# relay-unit-atmega.net
KiCad netlist of a schematic drawn in EAGLE
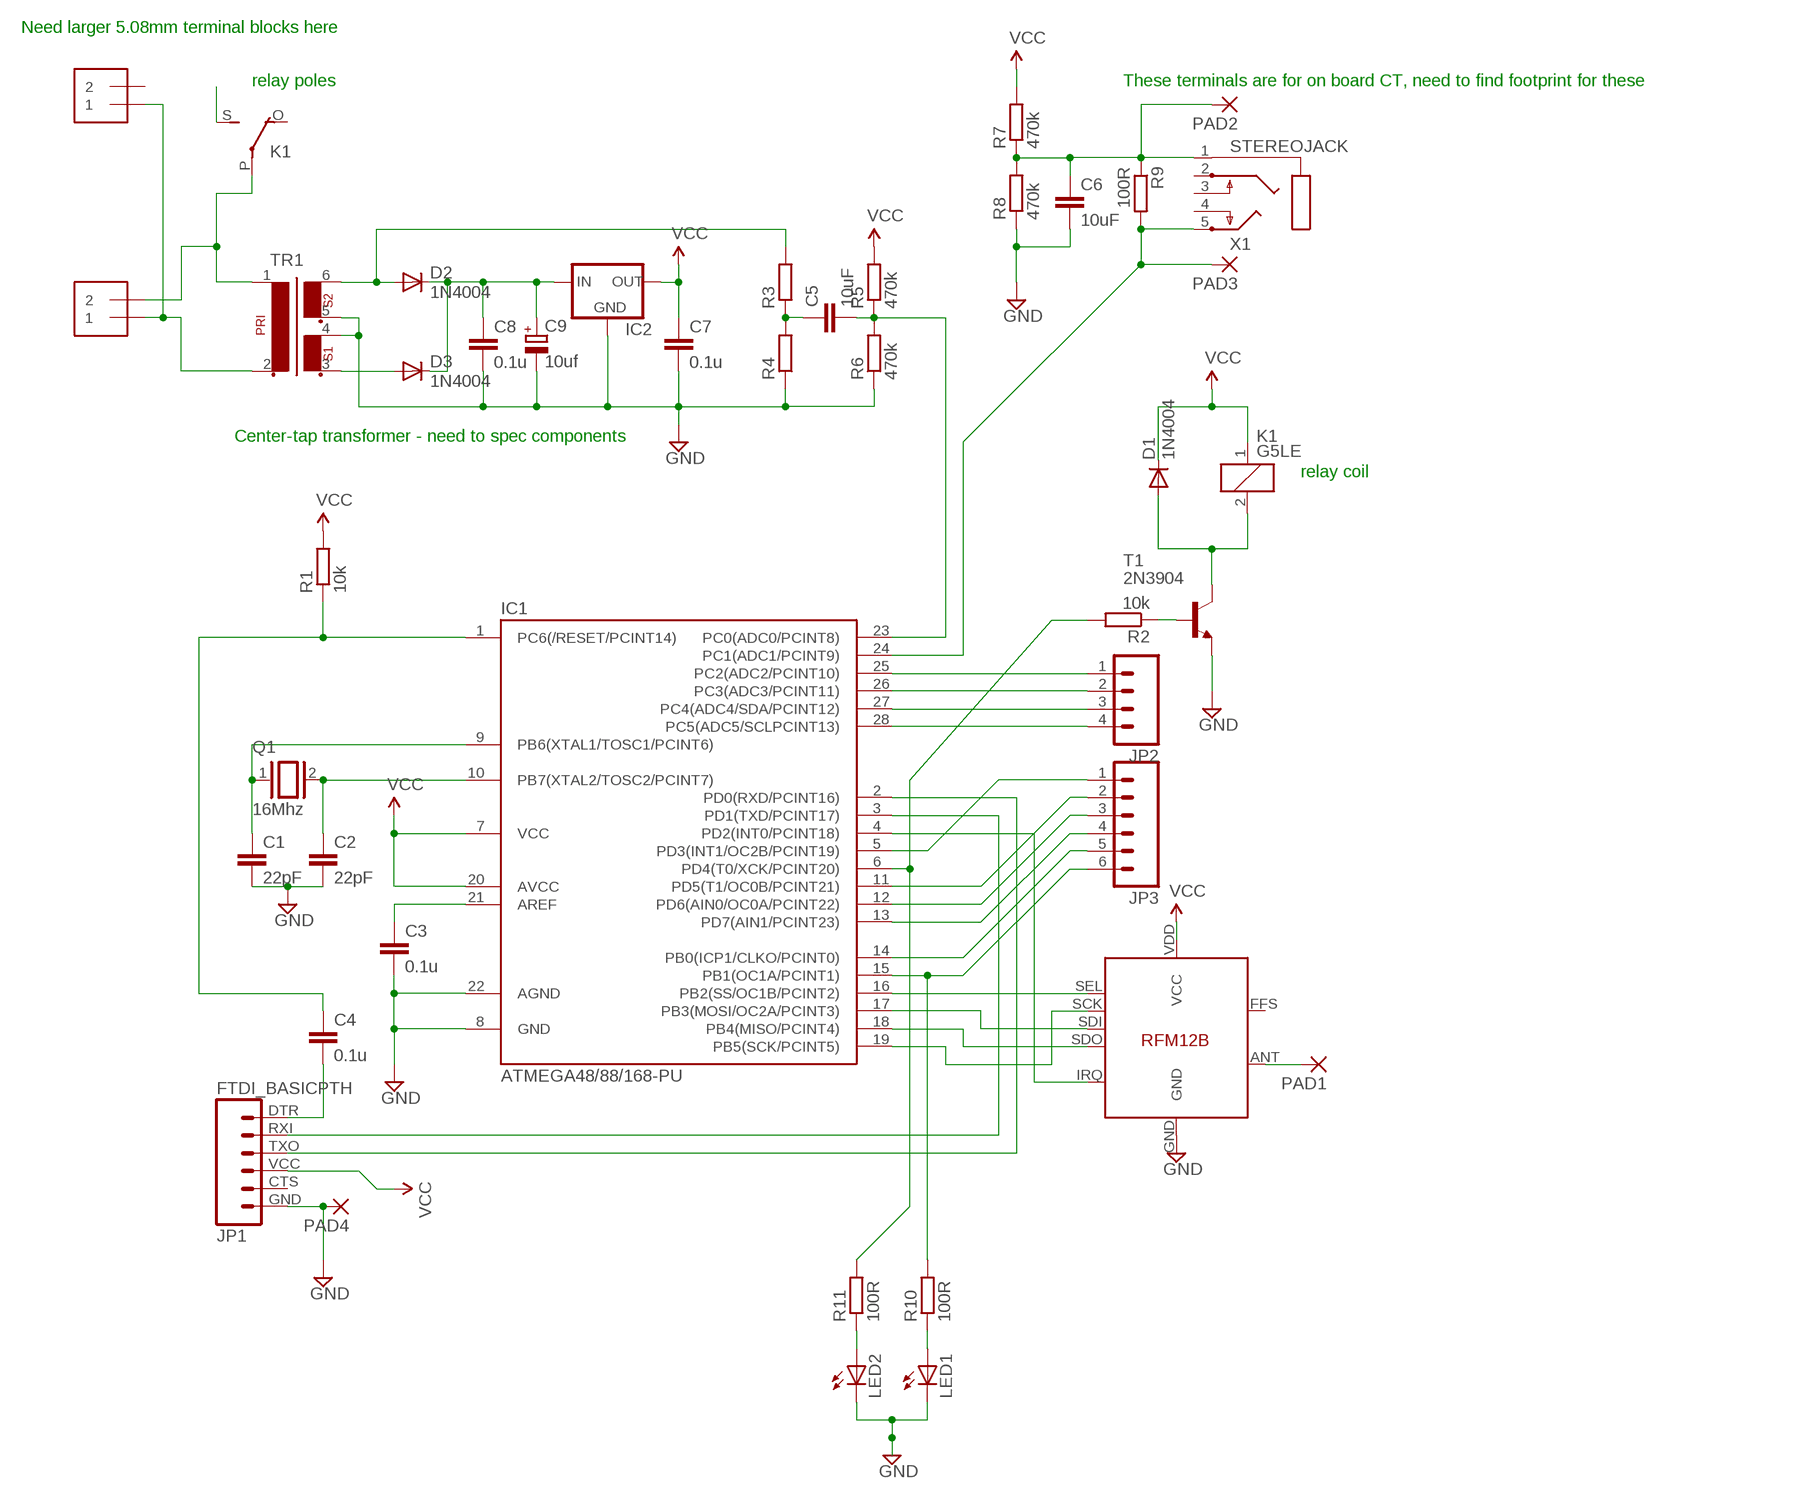
[diagram p0: schematic, sheet 1]

(export (version "E")
  (design (tool "Eeschema 10.0.6"))
  (components
    (comp (ref "C1")
      (value "22pF")
      (footprint "eagle-import:C2.5-2")
      (libsource (lib "eagle-import") (part "C2.5/2"))
    )
    (comp (ref "C2")
      (value "22pF")
      (footprint "eagle-import:C2.5-2")
      (libsource (lib "eagle-import") (part "C2.5/2"))
    )
    (comp (ref "C3")
      (value "0.1u")
      (footprint "eagle-import:C025-024X044")
      (libsource (lib "eagle-import") (part "C-EU025-024X044"))
    )
    (comp (ref "C4")
      (value "0.1u")
      (footprint "eagle-import:C025-024X044")
      (libsource (lib "eagle-import") (part "C-EU025-024X044"))
    )
    (comp (ref "C5")
      (value "10uF")
      (footprint "eagle-import:C025-024X044")
      (libsource (lib "eagle-import") (part "C-EU025-024X044"))
    )
    (comp (ref "C6")
      (value "10uF")
      (footprint "eagle-import:C025-024X044")
      (libsource (lib "eagle-import") (part "C-EU025-024X044"))
    )
    (comp (ref "C7")
      (value "0.1u")
      (footprint "eagle-import:C025-024X044")
      (libsource (lib "eagle-import") (part "C-EU025-024X044"))
    )
    (comp (ref "C8")
      (value "0.1u")
      (footprint "eagle-import:C025-024X044")
      (libsource (lib "eagle-import") (part "C-EU025-024X044"))
    )
    (comp (ref "C9")
      (value "10uf")
      (footprint "eagle-import:E1,8-4")
      (libsource (lib "eagle-import") (part "CPOL-EUE1.8-4"))
    )
    (comp (ref "D1")
      (value "1N4004")
      (footprint "eagle-import:DO41-10")
      (libsource (lib "eagle-import") (part "1N4004"))
    )
    (comp (ref "D2")
      (value "1N4004")
      (footprint "eagle-import:DO41-10")
      (libsource (lib "eagle-import") (part "1N4004"))
    )
    (comp (ref "D3")
      (value "1N4004")
      (footprint "eagle-import:DO41-10")
      (libsource (lib "eagle-import") (part "1N4004"))
    )
    (comp (ref "IC1")
      (value "ATMEGA48/88/168-PU")
      (footprint "eagle-import:DIL28-3")
      (libsource (lib "eagle-import") (part "ATMEGA48/88/168-PU"))
    )
    (comp (ref "IC2")
      (value "MCP1700TRI")
      (footprint "eagle-import:TO92")
      (libsource (lib "eagle-import") (part "MCP1700TRI"))
    )
    (comp (ref "J1")
      (value "1X2-3.5MM")
      (footprint "eagle-import:1X2-3.5MM")
      (libsource (lib "eagle-import") (part "1X2-3.5MM"))
    )
    (comp (ref "J2")
      (value "1X2-3.5MM")
      (footprint "eagle-import:1X2-3.5MM")
      (libsource (lib "eagle-import") (part "1X2-3.5MM"))
    )
    (comp (ref "JP1")
      (value "FTDI_BASICPTH")
      (footprint "eagle-import:FTDI_BASIC")
      (libsource (lib "eagle-import") (part "FTDI_BASICPTH"))
    )
    (comp (ref "JP2")
      (value "M04PTH")
      (footprint "eagle-import:1X04")
      (libsource (lib "eagle-import") (part "M04PTH"))
    )
    (comp (ref "JP3")
      (value "M06SIP")
      (footprint "eagle-import:1X06")
      (libsource (lib "eagle-import") (part "M06SIP"))
    )
    (comp (ref "K1")
      (value "G5LE")
      (footprint "eagle-import:G5LE")
      (libsource (lib "eagle-import") (part "G5LE"))
    )
    (comp (ref "LED1")
      (value "LED3MM")
      (footprint "eagle-import:LED3MM")
      (libsource (lib "eagle-import") (part "LED3MM"))
    )
    (comp (ref "LED2")
      (value "LED3MM")
      (footprint "eagle-import:LED3MM")
      (libsource (lib "eagle-import") (part "LED3MM"))
    )
    (comp (ref "PAD1")
      (value "1,6/0,8")
      (footprint "eagle-import:1,6_0,8")
      (libsource (lib "eagle-import") (part "1,6/0,8"))
    )
    (comp (ref "PAD2")
      (value "1,6/0,8")
      (footprint "eagle-import:1,6_0,8")
      (libsource (lib "eagle-import") (part "1,6/0,8"))
    )
    (comp (ref "PAD3")
      (value "1,6/0,8")
      (footprint "eagle-import:1,6_0,8")
      (libsource (lib "eagle-import") (part "1,6/0,8"))
    )
    (comp (ref "PAD4")
      (value "1,6/0,8")
      (footprint "eagle-import:1,6_0,8")
      (libsource (lib "eagle-import") (part "1,6/0,8"))
    )
    (comp (ref "Q1")
      (value "16Mhz")
      (footprint "eagle-import:QS")
      (libsource (lib "eagle-import") (part "XTAL/S"))
    )
    (comp (ref "R1")
      (value "10k")
      (footprint "eagle-import:0204_7")
      (libsource (lib "eagle-import") (part "R-EU_0204/7"))
    )
    (comp (ref "R2")
      (value "10k")
      (footprint "eagle-import:0204_7")
      (libsource (lib "eagle-import") (part "R-EU_0204/7"))
    )
    (comp (ref "R3")
      (value "R-EU_0204/7")
      (footprint "eagle-import:0204_7")
      (libsource (lib "eagle-import") (part "R-EU_0204/7"))
    )
    (comp (ref "R4")
      (value "R-EU_0204/7")
      (footprint "eagle-import:0204_7")
      (libsource (lib "eagle-import") (part "R-EU_0204/7"))
    )
    (comp (ref "R5")
      (value "470k")
      (footprint "eagle-import:0204_7")
      (libsource (lib "eagle-import") (part "R-EU_0204/7"))
    )
    (comp (ref "R6")
      (value "470k")
      (footprint "eagle-import:0204_7")
      (libsource (lib "eagle-import") (part "R-EU_0204/7"))
    )
    (comp (ref "R7")
      (value "470k")
      (footprint "eagle-import:0204_7")
      (libsource (lib "eagle-import") (part "R-EU_0204/7"))
    )
    (comp (ref "R8")
      (value "470k")
      (footprint "eagle-import:0204_7")
      (libsource (lib "eagle-import") (part "R-EU_0204/7"))
    )
    (comp (ref "R9")
      (value "100R")
      (footprint "eagle-import:0204_7")
      (libsource (lib "eagle-import") (part "R-EU_0204/7"))
    )
    (comp (ref "R10")
      (value "100R")
      (footprint "eagle-import:0204_7")
      (libsource (lib "eagle-import") (part "R-EU_0204/7"))
    )
    (comp (ref "R11")
      (value "100R")
      (footprint "eagle-import:0204_7")
      (libsource (lib "eagle-import") (part "R-EU_0204/7"))
    )
    (comp (ref "T1")
      (value "2N3904")
      (footprint "eagle-import:TO92")
      (libsource (lib "eagle-import") (part "2N3904"))
    )
    (comp (ref "TR1")
      (value "VP32")
      (footprint "eagle-import:VP32")
      (libsource (lib "eagle-import") (part "VP32"))
    )
    (comp (ref "U$1")
      (value "RFM12B")
      (footprint "eagle-import:RFM12B")
      (libsource (lib "eagle-import") (part "RFM12B"))
    )
    (comp (ref "X1")
      (value "STEREOJACK")
      (footprint "eagle-import:STX3100")
      (libsource (lib "eagle-import") (part "STEREOJACK"))
    )
  )
  (nets
    (net (code "1") (name "GND") (class "Default")
      (node (ref "C1") (pin "2") (pinfunction "2_2") (pintype "passive"))
      (node (ref "C2") (pin "2") (pinfunction "2_2") (pintype "passive"))
      (node (ref "C3") (pin "2") (pinfunction "2_2") (pintype "passive"))
      (node (ref "C6") (pin "2") (pinfunction "2_2") (pintype "passive"))
      (node (ref "C7") (pin "2") (pinfunction "2_2") (pintype "passive"))
      (node (ref "C8") (pin "2") (pinfunction "2_2") (pintype "passive"))
      (node (ref "C9") (pin "-") (pinfunction "-_-") (pintype "passive"))
      (node (ref "IC1") (pin "22") (pinfunction "AGND_22") (pintype "power_in"))
      (node (ref "IC1") (pin "8") (pinfunction "GND_8") (pintype "power_in"))
      (node (ref "IC2") (pin "1") (pinfunction "GND_1") (pintype "input"))
      (node (ref "JP1") (pin "GND") (pinfunction "6_GND") (pintype "passive"))
      (node (ref "LED1") (pin "K") (pinfunction "C_K") (pintype "passive"))
      (node (ref "LED2") (pin "K") (pinfunction "C_K") (pintype "passive"))
      (node (ref "PAD4") (pin "1") (pinfunction "P_1") (pintype "passive"))
      (node (ref "R4") (pin "1") (pinfunction "1_1") (pintype "passive"))
      (node (ref "R6") (pin "1") (pinfunction "1_1") (pintype "passive"))
      (node (ref "R8") (pin "1") (pinfunction "1_1") (pintype "passive"))
      (node (ref "T1") (pin "3") (pinfunction "E_3") (pintype "passive"))
      (node (ref "TR1") (pin "4") (pinfunction "4_4") (pintype "passive"))
      (node (ref "TR1") (pin "5") (pinfunction "5_5") (pintype "passive"))
      (node (ref "U$1") (pin "GND") (pinfunction "GND_GND") (pintype "power_in"))
    )
    (net (code "2") (name "Net-(C5-Pad1)") (class "Default")
      (node (ref "C5") (pin "1") (pinfunction "1_1") (pintype "passive"))
      (node (ref "R3") (pin "1") (pinfunction "1_1") (pintype "passive"))
      (node (ref "R4") (pin "2") (pinfunction "2_2") (pintype "passive"))
    )
    (net (code "3") (name "Net-(D2-PadA)") (class "Default")
      (node (ref "D2") (pin "A") (pinfunction "A_A") (pintype "passive"))
      (node (ref "R3") (pin "2") (pinfunction "2_2") (pintype "passive"))
      (node (ref "TR1") (pin "6") (pinfunction "6_6") (pintype "passive"))
    )
    (net (code "4") (name "Net-(D3-PadA)") (class "Default")
      (node (ref "D3") (pin "A") (pinfunction "A_A") (pintype "passive"))
      (node (ref "TR1") (pin "3") (pinfunction "3_3") (pintype "passive"))
    )
    (net (code "5") (name "Net-(IC1-AREF)") (class "Default")
      (node (ref "C3") (pin "1") (pinfunction "1_1") (pintype "passive"))
      (node (ref "IC1") (pin "21") (pinfunction "AREF_21") (pintype "passive"))
    )
    (net (code "6") (name "Net-(IC1-PB0(ICP1{slash}CLKO{slash}PCINT0))") (class "Default")
      (node (ref "IC1") (pin "14") (pinfunction "PB0(ICP1/CLKO/PCINT0)_14") (pintype "bidirectional"))
      (node (ref "JP3") (pin "5") (pinfunction "5_5") (pintype "passive"))
    )
    (net (code "7") (name "Net-(IC1-PB1(OC1A{slash}PCINT1))") (class "Default")
      (node (ref "IC1") (pin "15") (pinfunction "PB1(OC1A/PCINT1)_15") (pintype "bidirectional"))
      (node (ref "JP3") (pin "6") (pinfunction "6_6") (pintype "passive"))
      (node (ref "R10") (pin "2") (pinfunction "2_2") (pintype "passive"))
    )
    (net (code "8") (name "Net-(IC1-PB2(SS{slash}OC1B{slash}PCINT2))") (class "Default")
      (node (ref "IC1") (pin "16") (pinfunction "PB2(SS/OC1B/PCINT2)_16") (pintype "bidirectional"))
      (node (ref "U$1") (pin "SEL") (pinfunction "SEL_SEL") (pintype "input"))
    )
    (net (code "9") (name "Net-(IC1-PB3(MOSI{slash}OC2A{slash}PCINT3))") (class "Default")
      (node (ref "IC1") (pin "17") (pinfunction "PB3(MOSI/OC2A/PCINT3)_17") (pintype "bidirectional"))
      (node (ref "U$1") (pin "SDI") (pinfunction "SDI_SDI") (pintype "input"))
    )
    (net (code "10") (name "Net-(IC1-PB4(MISO{slash}PCINT4))") (class "Default")
      (node (ref "IC1") (pin "18") (pinfunction "PB4(MISO/PCINT4)_18") (pintype "bidirectional"))
      (node (ref "U$1") (pin "SDO") (pinfunction "SDO_SDO") (pintype "output"))
    )
    (net (code "11") (name "Net-(IC1-PB5(SCK{slash}PCINT5))") (class "Default")
      (node (ref "IC1") (pin "19") (pinfunction "PB5(SCK/PCINT5)_19") (pintype "bidirectional"))
      (node (ref "U$1") (pin "SCK") (pinfunction "SCK_SCK") (pintype "input"))
    )
    (net (code "12") (name "Net-(IC1-PB6(XTAL1{slash}TOSC1{slash}PCINT6))") (class "Default")
      (node (ref "C1") (pin "1") (pinfunction "1_1") (pintype "passive"))
      (node (ref "IC1") (pin "9") (pinfunction "PB6(XTAL1/TOSC1/PCINT6)_9") (pintype "bidirectional"))
      (node (ref "Q1") (pin "1") (pinfunction "1_1") (pintype "passive"))
    )
    (net (code "13") (name "Net-(IC1-PB7(XTAL2{slash}TOSC2{slash}PCINT7))") (class "Default")
      (node (ref "C2") (pin "1") (pinfunction "1_1") (pintype "passive"))
      (node (ref "IC1") (pin "10") (pinfunction "PB7(XTAL2/TOSC2/PCINT7)_10") (pintype "bidirectional"))
      (node (ref "Q1") (pin "2") (pinfunction "2_2") (pintype "passive"))
    )
    (net (code "14") (name "Net-(IC1-PC0(ADC0{slash}PCINT8))") (class "Default")
      (node (ref "C5") (pin "2") (pinfunction "2_2") (pintype "passive"))
      (node (ref "IC1") (pin "23") (pinfunction "PC0(ADC0/PCINT8)_23") (pintype "bidirectional"))
      (node (ref "R5") (pin "1") (pinfunction "1_1") (pintype "passive"))
      (node (ref "R6") (pin "2") (pinfunction "2_2") (pintype "passive"))
    )
    (net (code "15") (name "Net-(IC1-PC1(ADC1{slash}PCINT9))") (class "Default")
      (node (ref "IC1") (pin "24") (pinfunction "PC1(ADC1/PCINT9)_24") (pintype "bidirectional"))
      (node (ref "PAD3") (pin "1") (pinfunction "P_1") (pintype "passive"))
      (node (ref "R9") (pin "2") (pinfunction "2_2") (pintype "passive"))
      (node (ref "X1") (pin "5") (pinfunction "5_5") (pintype "passive"))
    )
    (net (code "16") (name "Net-(IC1-PC2(ADC2{slash}PCINT10))") (class "Default")
      (node (ref "IC1") (pin "25") (pinfunction "PC2(ADC2/PCINT10)_25") (pintype "bidirectional"))
      (node (ref "JP2") (pin "1") (pinfunction "1_1") (pintype "passive"))
    )
    (net (code "17") (name "Net-(IC1-PC3(ADC3{slash}PCINT11))") (class "Default")
      (node (ref "IC1") (pin "26") (pinfunction "PC3(ADC3/PCINT11)_26") (pintype "bidirectional"))
      (node (ref "JP2") (pin "2") (pinfunction "2_2") (pintype "passive"))
    )
    (net (code "18") (name "Net-(IC1-PC4(ADC4{slash}SDA{slash}PCINT12))") (class "Default")
      (node (ref "IC1") (pin "27") (pinfunction "PC4(ADC4/SDA/PCINT12)_27") (pintype "bidirectional"))
      (node (ref "JP2") (pin "3") (pinfunction "3_3") (pintype "passive"))
    )
    (net (code "19") (name "Net-(IC1-PC5(ADC5{slash}SCLPCINT13))") (class "Default")
      (node (ref "IC1") (pin "28") (pinfunction "PC5(ADC5/SCLPCINT13)_28") (pintype "bidirectional"))
      (node (ref "JP2") (pin "4") (pinfunction "4_4") (pintype "passive"))
    )
    (net (code "20") (name "Net-(IC1-PC6({slash}RESET{slash}PCINT14))") (class "Default")
      (node (ref "C4") (pin "1") (pinfunction "1_1") (pintype "passive"))
      (node (ref "IC1") (pin "1") (pinfunction "PC6(/RESET/PCINT14)_1") (pintype "bidirectional"))
      (node (ref "R1") (pin "1") (pinfunction "1_1") (pintype "passive"))
    )
    (net (code "21") (name "Net-(IC1-PD0(RXD{slash}PCINT16))") (class "Default")
      (node (ref "IC1") (pin "2") (pinfunction "PD0(RXD/PCINT16)_2") (pintype "bidirectional"))
      (node (ref "JP1") (pin "TXO") (pinfunction "3_TXO") (pintype "passive"))
    )
    (net (code "22") (name "Net-(IC1-PD1(TXD{slash}PCINT17))") (class "Default")
      (node (ref "IC1") (pin "3") (pinfunction "PD1(TXD/PCINT17)_3") (pintype "bidirectional"))
      (node (ref "JP1") (pin "RXI") (pinfunction "2_RXI") (pintype "passive"))
    )
    (net (code "23") (name "Net-(IC1-PD2(INT0{slash}PCINT18))") (class "Default")
      (node (ref "IC1") (pin "4") (pinfunction "PD2(INT0/PCINT18)_4") (pintype "bidirectional"))
      (node (ref "U$1") (pin "IRQ") (pinfunction "IRQ_IRQ") (pintype "open_collector"))
    )
    (net (code "24") (name "Net-(IC1-PD3(INT1{slash}OC2B{slash}PCINT19))") (class "Default")
      (node (ref "IC1") (pin "5") (pinfunction "PD3(INT1/OC2B/PCINT19)_5") (pintype "bidirectional"))
      (node (ref "JP3") (pin "1") (pinfunction "1_1") (pintype "passive"))
    )
    (net (code "25") (name "Net-(IC1-PD4(T0{slash}XCK{slash}PCINT20))") (class "Default")
      (node (ref "IC1") (pin "6") (pinfunction "PD4(T0/XCK/PCINT20)_6") (pintype "bidirectional"))
      (node (ref "R11") (pin "2") (pinfunction "2_2") (pintype "passive"))
      (node (ref "R2") (pin "2") (pinfunction "2_2") (pintype "passive"))
    )
    (net (code "26") (name "Net-(IC1-PD5(T1{slash}OC0B{slash}PCINT21))") (class "Default")
      (node (ref "IC1") (pin "11") (pinfunction "PD5(T1/OC0B/PCINT21)_11") (pintype "bidirectional"))
      (node (ref "JP3") (pin "2") (pinfunction "2_2") (pintype "passive"))
    )
    (net (code "27") (name "Net-(IC1-PD6(AIN0{slash}OC0A{slash}PCINT22))") (class "Default")
      (node (ref "IC1") (pin "12") (pinfunction "PD6(AIN0/OC0A/PCINT22)_12") (pintype "bidirectional"))
      (node (ref "JP3") (pin "3") (pinfunction "3_3") (pintype "passive"))
    )
    (net (code "28") (name "Net-(IC1-PD7(AIN1{slash}PCINT23))") (class "Default")
      (node (ref "IC1") (pin "13") (pinfunction "PD7(AIN1/PCINT23)_13") (pintype "bidirectional"))
      (node (ref "JP3") (pin "4") (pinfunction "4_4") (pintype "passive"))
    )
    (net (code "29") (name "Net-(IC2-IN)") (class "Default")
      (node (ref "C8") (pin "1") (pinfunction "1_1") (pintype "passive"))
      (node (ref "C9") (pin "+") (pinfunction "+_+") (pintype "passive"))
      (node (ref "D2") (pin "C") (pinfunction "C_C") (pintype "passive"))
      (node (ref "D3") (pin "C") (pinfunction "C_C") (pintype "passive"))
      (node (ref "IC2") (pin "2") (pinfunction "IN_2") (pintype "input"))
    )
    (net (code "30") (name "Net-(J1-Pad1)") (class "Default")
      (node (ref "J1") (pin "1") (pinfunction "1_1") (pintype "passive"))
      (node (ref "J2") (pin "1") (pinfunction "1_1") (pintype "passive"))
      (node (ref "TR1") (pin "2") (pinfunction "2_2") (pintype "passive"))
    )
    (net (code "31") (name "Net-(J2-Pad2)") (class "Default")
      (node (ref "J2") (pin "2") (pinfunction "2_2") (pintype "passive"))
      (node (ref "K1") (pin "P") (pinfunction "P_P") (pintype "passive"))
      (node (ref "TR1") (pin "1") (pinfunction "1_1") (pintype "passive"))
    )
    (net (code "32") (name "Net-(JP1-1)") (class "Default")
      (node (ref "C4") (pin "2") (pinfunction "2_2") (pintype "passive"))
      (node (ref "JP1") (pin "DTR") (pinfunction "1_DTR") (pintype "passive"))
    )
    (net (code "33") (name "Net-(LED1-PadA)") (class "Default")
      (node (ref "LED1") (pin "A") (pinfunction "A_A") (pintype "passive"))
      (node (ref "R10") (pin "1") (pinfunction "1_1") (pintype "passive"))
    )
    (net (code "34") (name "Net-(LED2-PadA)") (class "Default")
      (node (ref "LED2") (pin "A") (pinfunction "A_A") (pintype "passive"))
      (node (ref "R11") (pin "1") (pinfunction "1_1") (pintype "passive"))
    )
    (net (code "35") (name "Net-(PAD1-P)") (class "Default")
      (node (ref "PAD1") (pin "1") (pinfunction "P_1") (pintype "passive"))
      (node (ref "U$1") (pin "ANT") (pinfunction "ANT_ANT") (pintype "passive"))
    )
    (net (code "36") (name "Net-(PAD2-P)") (class "Default")
      (node (ref "C6") (pin "1") (pinfunction "1_1") (pintype "passive"))
      (node (ref "PAD2") (pin "1") (pinfunction "P_1") (pintype "passive"))
      (node (ref "R7") (pin "1") (pinfunction "1_1") (pintype "passive"))
      (node (ref "R8") (pin "2") (pinfunction "2_2") (pintype "passive"))
      (node (ref "R9") (pin "1") (pinfunction "1_1") (pintype "passive"))
      (node (ref "X1") (pin "1") (pinfunction "1_1") (pintype "passive"))
    )
    (net (code "37") (name "Net-(T1-B)") (class "Default")
      (node (ref "R2") (pin "1") (pinfunction "1_1") (pintype "passive"))
      (node (ref "T1") (pin "2") (pinfunction "B_2") (pintype "passive"))
    )
    (net (code "38") (name "Net-(T1-C)") (class "Default")
      (node (ref "D1") (pin "A") (pinfunction "A_A") (pintype "passive"))
      (node (ref "K1") (pin "2") (pinfunction "2_2") (pintype "passive"))
      (node (ref "T1") (pin "1") (pinfunction "C_1") (pintype "passive"))
    )
    (net (code "39") (name "VCC") (class "Default")
      (node (ref "C7") (pin "1") (pinfunction "1_1") (pintype "passive"))
      (node (ref "D1") (pin "C") (pinfunction "C_C") (pintype "passive"))
      (node (ref "IC1") (pin "20") (pinfunction "AVCC_20") (pintype "passive"))
      (node (ref "IC1") (pin "7") (pinfunction "VCC_7") (pintype "power_in"))
      (node (ref "IC2") (pin "3") (pinfunction "OUT_3") (pintype "passive"))
      (node (ref "JP1") (pin "VCC") (pinfunction "4_VCC") (pintype "passive"))
      (node (ref "K1") (pin "1") (pinfunction "1_1") (pintype "passive"))
      (node (ref "R1") (pin "2") (pinfunction "2_2") (pintype "passive"))
      (node (ref "R5") (pin "2") (pinfunction "2_2") (pintype "passive"))
      (node (ref "R7") (pin "2") (pinfunction "2_2") (pintype "passive"))
      (node (ref "U$1") (pin "VDD") (pinfunction "VCC_VDD") (pintype "power_in"))
    )
    (net (code "40") (name "unconnected-(J1-Pad2)") (class "Default")
      (node (ref "J1") (pin "2") (pinfunction "2_2") (pintype "passive"))
    )
    (net (code "41") (name "unconnected-(JP1-5-PadCTS)") (class "Default")
      (node (ref "JP1") (pin "CTS") (pinfunction "5_CTS") (pintype "passive"))
    )
    (net (code "42") (name "unconnected-(K1-PadO)") (class "Default")
      (node (ref "K1") (pin "O") (pinfunction "O_O") (pintype "passive"))
    )
    (net (code "43") (name "unconnected-(K1-PadS)") (class "Default")
      (node (ref "K1") (pin "S") (pinfunction "S_S") (pintype "passive"))
    )
    (net (code "44") (name "unconnected-(U$1-PadFFS)") (class "Default")
      (node (ref "U$1") (pin "FFS") (pinfunction "FFS_FFS") (pintype "bidirectional"))
    )
    (net (code "45") (name "unconnected-(X1-Pad2)") (class "Default")
      (node (ref "X1") (pin "2") (pinfunction "2_2") (pintype "passive"))
    )
    (net (code "46") (name "unconnected-(X1-Pad3)") (class "Default")
      (node (ref "X1") (pin "3") (pinfunction "3_3") (pintype "passive"))
    )
    (net (code "47") (name "unconnected-(X1-Pad4)") (class "Default")
      (node (ref "X1") (pin "4") (pinfunction "4_4") (pintype "passive"))
    )
  )
)
